# ai_breakout_adns3080.net
KiCad netlist of a schematic drawn in EAGLE
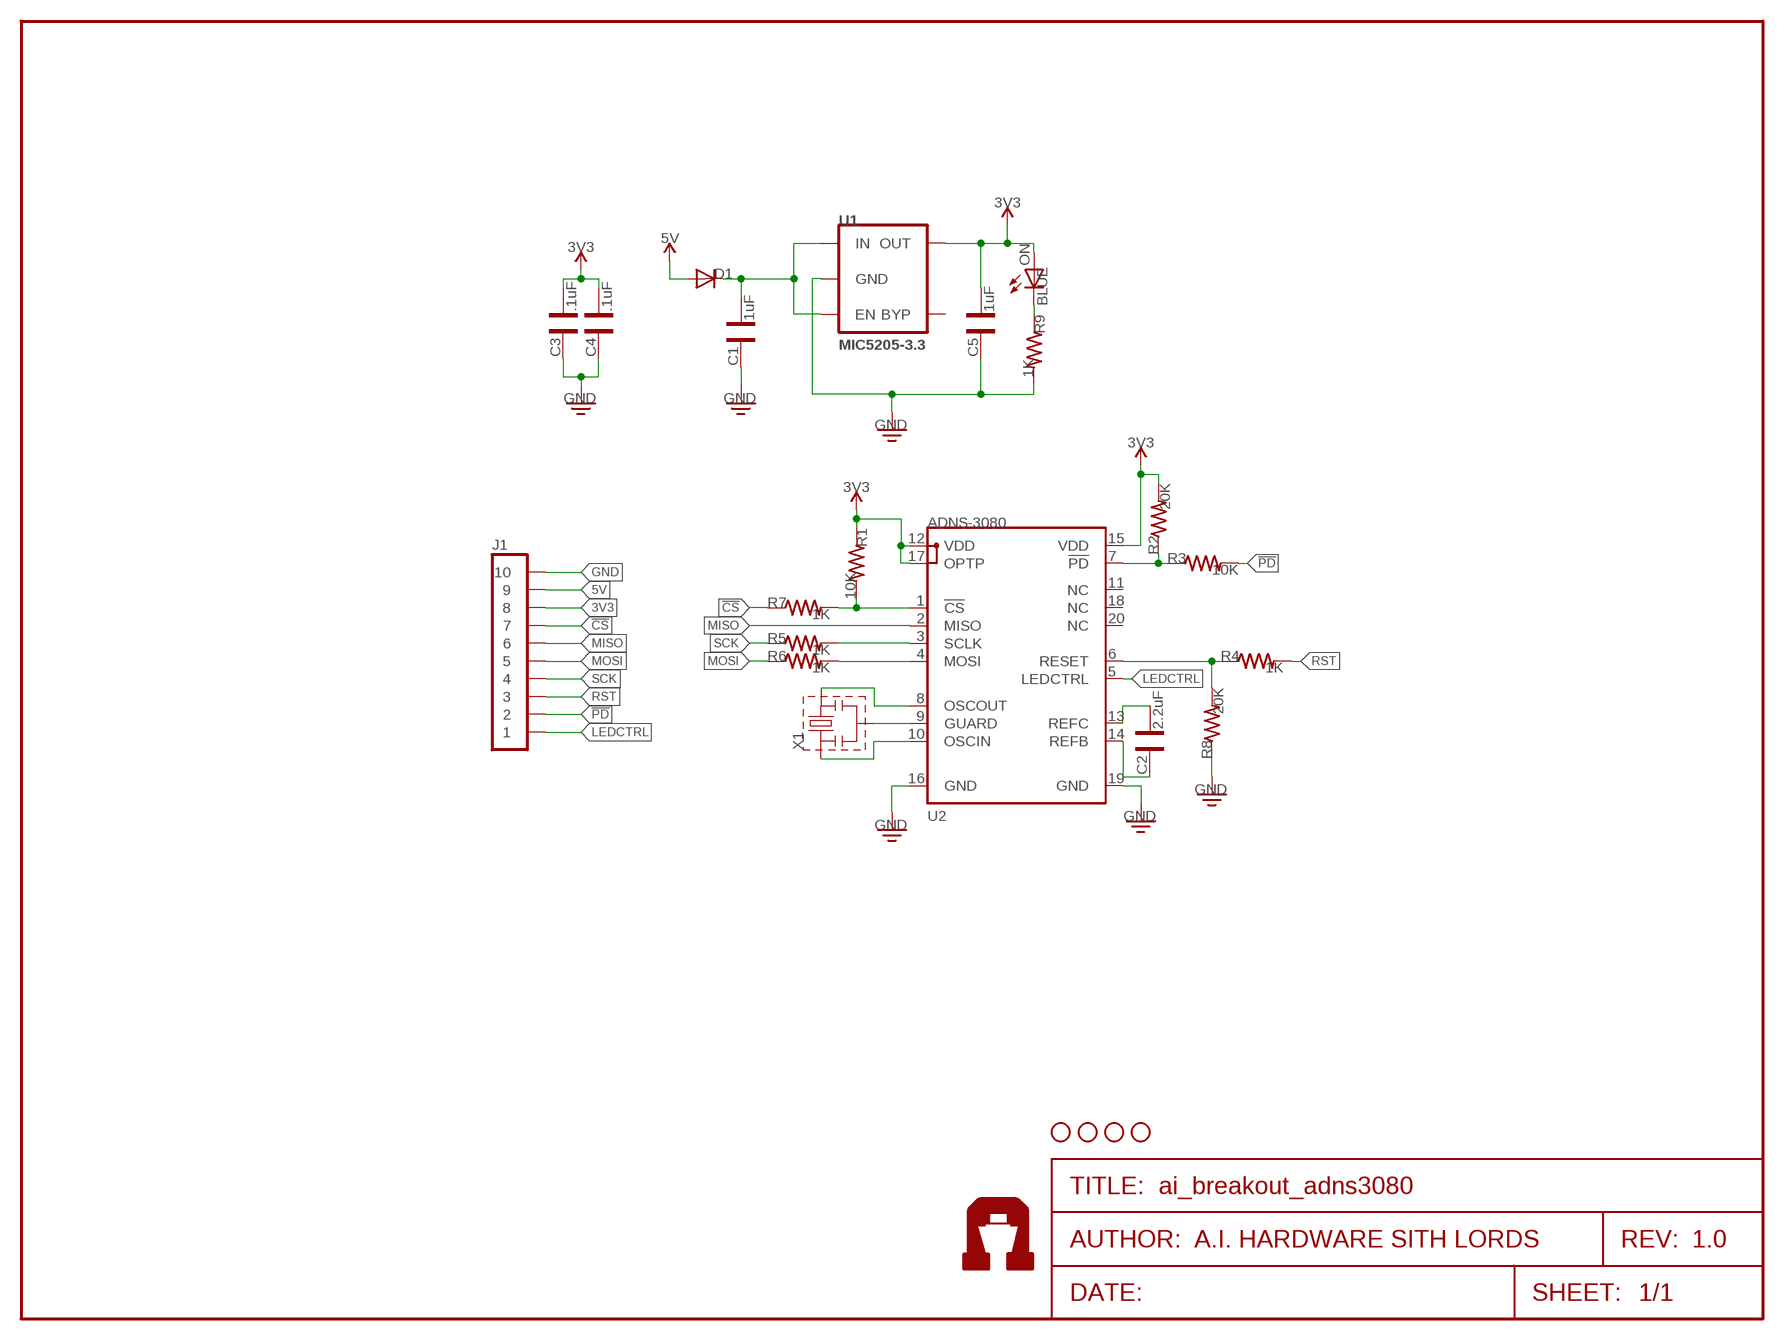
[diagram p0: schematic, sheet 1]

(export (version "E")
  (design (tool "Eeschema 10.0.6"))
  (components
    (comp (ref "C1")
      (value "1uF")
      (footprint "eagle-import:CAP-0603")
      (libsource (lib "eagle-import") (part "CAP0603"))
    )
    (comp (ref "C2")
      (value "2.2uF")
      (footprint "eagle-import:CAP-0603")
      (libsource (lib "eagle-import") (part "CAP0603"))
    )
    (comp (ref "C3")
      (value ".1uF")
      (footprint "eagle-import:CAP-0603")
      (libsource (lib "eagle-import") (part "CAP0603"))
    )
    (comp (ref "C4")
      (value ".1uF")
      (footprint "eagle-import:CAP-0603")
      (libsource (lib "eagle-import") (part "CAP0603"))
    )
    (comp (ref "C5")
      (value "1uF")
      (footprint "eagle-import:CAP-0603")
      (libsource (lib "eagle-import") (part "CAP0603"))
    )
    (comp (ref "D1")
      (value "DIODESMA-403D")
      (footprint "eagle-import:SMA-403D")
      (libsource (lib "eagle-import") (part "DIODESMA-403D"))
    )
    (comp (ref "J1")
      (value "1X10")
      (footprint "eagle-import:1X10")
      (libsource (lib "eagle-import") (part "1X10"))
    )
    (comp (ref "ON")
      (value "BLUE")
      (footprint "eagle-import:LED-0603")
      (libsource (lib "eagle-import") (part "LED0603"))
    )
    (comp (ref "R1")
      (value "10K")
      (footprint "eagle-import:RES-0603")
      (libsource (lib "eagle-import") (part "RES0603"))
    )
    (comp (ref "R2")
      (value "20K")
      (footprint "eagle-import:RES-0603")
      (libsource (lib "eagle-import") (part "RES0603"))
    )
    (comp (ref "R3")
      (value "10K")
      (footprint "eagle-import:RES-0603")
      (libsource (lib "eagle-import") (part "RES0603"))
    )
    (comp (ref "R4")
      (value "1K")
      (footprint "eagle-import:RES-0603")
      (libsource (lib "eagle-import") (part "RES0603"))
    )
    (comp (ref "R5")
      (value "1K")
      (footprint "eagle-import:RES-0603")
      (libsource (lib "eagle-import") (part "RES0603"))
    )
    (comp (ref "R6")
      (value "1K")
      (footprint "eagle-import:RES-0603")
      (libsource (lib "eagle-import") (part "RES0603"))
    )
    (comp (ref "R7")
      (value "1K")
      (footprint "eagle-import:RES-0603")
      (libsource (lib "eagle-import") (part "RES0603"))
    )
    (comp (ref "R8")
      (value "20K")
      (footprint "eagle-import:RES-0603")
      (libsource (lib "eagle-import") (part "RES0603"))
    )
    (comp (ref "R9")
      (value "1K")
      (footprint "eagle-import:RES-0603")
      (libsource (lib "eagle-import") (part "RES0603"))
    )
    (comp (ref "STANDOFF1")
      (value "STAND-OFF")
      (footprint "eagle-import:STAND-OFF")
      (libsource (lib "eagle-import") (part "STAND-OFF"))
    )
    (comp (ref "STANDOFF2")
      (value "STAND-OFF")
      (footprint "eagle-import:STAND-OFF")
      (libsource (lib "eagle-import") (part "STAND-OFF"))
    )
    (comp (ref "STANDOFF3")
      (value "STAND-OFF")
      (footprint "eagle-import:STAND-OFF")
      (libsource (lib "eagle-import") (part "STAND-OFF"))
    )
    (comp (ref "STANDOFF4")
      (value "STAND-OFF")
      (footprint "eagle-import:STAND-OFF")
      (libsource (lib "eagle-import") (part "STAND-OFF"))
    )
    (comp (ref "U$2")
      (value "AI-LOGOM")
      (footprint "eagle-import:AI-LOGO-M")
      (libsource (lib "eagle-import") (part "AI-LOGOM"))
    )
    (comp (ref "U$3")
      (value "AI-LOGOM")
      (footprint "eagle-import:AI-LOGO-M")
      (libsource (lib "eagle-import") (part "AI-LOGOM"))
    )
    (comp (ref "U1")
      (value "MIC5205-3.3")
      (footprint "eagle-import:SOT23-5")
      (libsource (lib "eagle-import") (part "MIC5205-3.3"))
    )
    (comp (ref "U2")
      (value "ADNS-3080")
      (footprint "eagle-import:ADNS-3080")
      (libsource (lib "eagle-import") (part "ADNS-3080"))
    )
    (comp (ref "X1")
      (value "RESON025X020")
      (footprint "eagle-import:RESON-SMD-025X020")
      (libsource (lib "eagle-import") (part "RESON025X020"))
    )
  )
  (nets
    (net (code "1") (name "/~{CS}") (class "Default")
      (node (ref "J1") (pin "7") (pinfunction "7_7") (pintype "bidirectional"))
      (node (ref "R7") (pin "1") (pinfunction "1_1") (pintype "passive"))
    )
    (net (code "2") (name "/~{PD}") (class "Default")
      (node (ref "J1") (pin "2") (pinfunction "2_2") (pintype "bidirectional"))
      (node (ref "R3") (pin "2") (pinfunction "2_2") (pintype "passive"))
    )
    (net (code "3") (name "3V3") (class "Default")
      (node (ref "C3") (pin "1") (pinfunction "1_1") (pintype "passive"))
      (node (ref "C4") (pin "1") (pinfunction "1_1") (pintype "passive"))
      (node (ref "C5") (pin "1") (pinfunction "1_1") (pintype "passive"))
      (node (ref "J1") (pin "8") (pinfunction "8_8") (pintype "bidirectional"))
      (node (ref "ON") (pin "A") (pinfunction "A_A") (pintype "passive"))
      (node (ref "R1") (pin "1") (pinfunction "1_1") (pintype "passive"))
      (node (ref "R2") (pin "2") (pinfunction "2_2") (pintype "passive"))
      (node (ref "U1") (pin "5") (pinfunction "OUT_5") (pintype "passive"))
      (node (ref "U2") (pin "12") (pinfunction "VDD_12") (pintype "power_in"))
      (node (ref "U2") (pin "15") (pinfunction "VDD_15") (pintype "power_in"))
      (node (ref "U2") (pin "17") (pinfunction "OPTP_17") (pintype "open_collector"))
    )
    (net (code "4") (name "5V") (class "Default")
      (node (ref "D1") (pin "A") (pinfunction "A_A") (pintype "passive"))
      (node (ref "J1") (pin "9") (pinfunction "9_9") (pintype "bidirectional"))
    )
    (net (code "5") (name "GND") (class "Default")
      (node (ref "C1") (pin "2") (pinfunction "2_2") (pintype "passive"))
      (node (ref "C3") (pin "2") (pinfunction "2_2") (pintype "passive"))
      (node (ref "C4") (pin "2") (pinfunction "2_2") (pintype "passive"))
      (node (ref "C5") (pin "2") (pinfunction "2_2") (pintype "passive"))
      (node (ref "J1") (pin "10") (pinfunction "10_10") (pintype "bidirectional"))
      (node (ref "R8") (pin "1") (pinfunction "1_1") (pintype "passive"))
      (node (ref "R9") (pin "2") (pinfunction "2_2") (pintype "passive"))
      (node (ref "U1") (pin "2") (pinfunction "GND_2") (pintype "input"))
      (node (ref "U2") (pin "16") (pinfunction "GND_16") (pintype "power_in"))
      (node (ref "U2") (pin "19") (pinfunction "GND_19") (pintype "power_in"))
    )
    (net (code "6") (name "LEDCTRL") (class "Default")
      (node (ref "J1") (pin "1") (pinfunction "1_1") (pintype "bidirectional"))
      (node (ref "U2") (pin "5") (pinfunction "LEDCTRL_5") (pintype "output"))
    )
    (net (code "7") (name "MISO") (class "Default")
      (node (ref "J1") (pin "6") (pinfunction "6_6") (pintype "bidirectional"))
      (node (ref "U2") (pin "2") (pinfunction "MISO_2") (pintype "output"))
    )
    (net (code "8") (name "MOSI") (class "Default")
      (node (ref "J1") (pin "5") (pinfunction "5_5") (pintype "bidirectional"))
      (node (ref "R6") (pin "1") (pinfunction "1_1") (pintype "passive"))
    )
    (net (code "9") (name "Net-(ON-PadC)") (class "Default")
      (node (ref "ON") (pin "C") (pinfunction "C_C") (pintype "passive"))
      (node (ref "R9") (pin "1") (pinfunction "1_1") (pintype "passive"))
    )
    (net (code "10") (name "Net-(U1-EN)") (class "Default")
      (node (ref "C1") (pin "1") (pinfunction "1_1") (pintype "passive"))
      (node (ref "D1") (pin "C") (pinfunction "C_C") (pintype "passive"))
      (node (ref "U1") (pin "1") (pinfunction "IN_1") (pintype "input"))
      (node (ref "U1") (pin "3") (pinfunction "EN_3") (pintype "input"))
    )
    (net (code "11") (name "Net-(U2-GUARD)") (class "Default")
      (node (ref "U2") (pin "9") (pinfunction "GUARD_9") (pintype "power_in"))
      (node (ref "X1") (pin "2") (pinfunction "2_2") (pintype "passive"))
    )
    (net (code "12") (name "Net-(U2-MOSI)") (class "Default")
      (node (ref "R6") (pin "2") (pinfunction "2_2") (pintype "passive"))
      (node (ref "U2") (pin "4") (pinfunction "MOSI_4") (pintype "input"))
    )
    (net (code "13") (name "Net-(U2-OSCIN)") (class "Default")
      (node (ref "U2") (pin "10") (pinfunction "OSCIN_10") (pintype "input"))
      (node (ref "X1") (pin "1") (pinfunction "1_1") (pintype "passive"))
    )
    (net (code "14") (name "Net-(U2-OSCOUT)") (class "Default")
      (node (ref "U2") (pin "8") (pinfunction "OSCOUT_8") (pintype "output"))
      (node (ref "X1") (pin "3") (pinfunction "3_3") (pintype "passive"))
    )
    (net (code "15") (name "Net-(U2-REFB)") (class "Default")
      (node (ref "C2") (pin "2") (pinfunction "2_2") (pintype "passive"))
      (node (ref "U2") (pin "14") (pinfunction "REFB_14") (pintype "input"))
    )
    (net (code "16") (name "Net-(U2-REFC)") (class "Default")
      (node (ref "C2") (pin "1") (pinfunction "1_1") (pintype "passive"))
      (node (ref "U2") (pin "13") (pinfunction "REFC_13") (pintype "input"))
    )
    (net (code "17") (name "Net-(U2-RESET)") (class "Default")
      (node (ref "R4") (pin "1") (pinfunction "1_1") (pintype "passive"))
      (node (ref "R8") (pin "2") (pinfunction "2_2") (pintype "passive"))
      (node (ref "U2") (pin "6") (pinfunction "RESET_6") (pintype "input"))
    )
    (net (code "18") (name "Net-(U2-SCLK)") (class "Default")
      (node (ref "R5") (pin "2") (pinfunction "2_2") (pintype "passive"))
      (node (ref "U2") (pin "3") (pinfunction "SCLK_3") (pintype "input"))
    )
    (net (code "19") (name "Net-(U2-~{CS})") (class "Default")
      (node (ref "R1") (pin "2") (pinfunction "2_2") (pintype "passive"))
      (node (ref "R7") (pin "2") (pinfunction "2_2") (pintype "passive"))
      (node (ref "U2") (pin "1") (pinfunction "~{CS}_1") (pintype "input"))
    )
    (net (code "20") (name "Net-(U2-~{PD})") (class "Default")
      (node (ref "R2") (pin "1") (pinfunction "1_1") (pintype "passive"))
      (node (ref "R3") (pin "1") (pinfunction "1_1") (pintype "passive"))
      (node (ref "U2") (pin "7") (pinfunction "~{PD}_7") (pintype "input"))
    )
    (net (code "21") (name "RST") (class "Default")
      (node (ref "J1") (pin "3") (pinfunction "3_3") (pintype "bidirectional"))
      (node (ref "R4") (pin "2") (pinfunction "2_2") (pintype "passive"))
    )
    (net (code "22") (name "SCK") (class "Default")
      (node (ref "J1") (pin "4") (pinfunction "4_4") (pintype "bidirectional"))
      (node (ref "R5") (pin "1") (pinfunction "1_1") (pintype "passive"))
    )
    (net (code "23") (name "unconnected-(U1-BYP-Pad4)") (class "Default")
      (node (ref "U1") (pin "4") (pinfunction "BYP_4") (pintype "input"))
    )
    (net (code "24") (name "unconnected-(U2-NC-Pad11)") (class "Default")
      (node (ref "U2") (pin "11") (pinfunction "NC_11") (pintype "no_connect"))
    )
    (net (code "25") (name "unconnected-(U2-NC-Pad18)") (class "Default")
      (node (ref "U2") (pin "18") (pinfunction "NC_18") (pintype "no_connect"))
    )
    (net (code "26") (name "unconnected-(U2-NC-Pad20)") (class "Default")
      (node (ref "U2") (pin "20") (pinfunction "NC_20") (pintype "no_connect"))
    )
  )
)
